# OpAMP_Sensor.net
KiCad netlist of a schematic drawn in Altium Designer
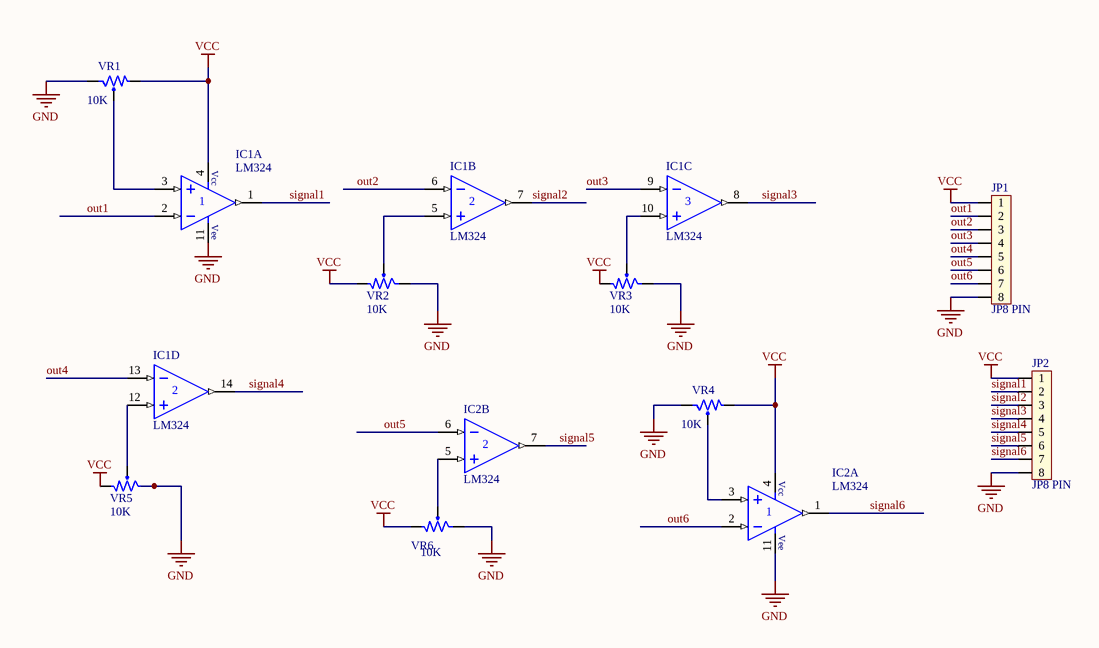
[diagram p0: OpAMP_Sensor.SchDoc]

(export (version "E")
  (design (tool "Eeschema 10.0.6"))
  (components
    (comp (ref "IC1")
      (value "LM324")
      (footprint "DIP14/W0.3")
      (description "Op x 4")
      (libsource (lib "syhaunguyen") (part "LM324"))
    )
    (comp (ref "IC2")
      (value "LM324")
      (footprint "DIP14/W0.3")
      (description "Op x 4")
      (libsource (lib "syhaunguyen") (part "LM324"))
    )
    (comp (ref "JP1") (value "JP8 PIN") (footprint "JP8") (libsource (lib "syhaunguyen") (part "JP8")))
    (comp (ref "JP2") (value "JP8 PIN") (footprint "JP8") (libsource (lib "syhaunguyen") (part "JP8")))
    (comp (ref "VR1")
      (value "10K")
      (footprint "VR")
      (description "Var Resistor")
      (libsource (lib "syhaunguyen") (part "VR1"))
    )
    (comp (ref "VR2")
      (value "10K")
      (footprint "VR")
      (description "Var Resistor")
      (libsource (lib "syhaunguyen") (part "VR1"))
    )
    (comp (ref "VR3")
      (value "10K")
      (footprint "VR")
      (description "Var Resistor")
      (libsource (lib "syhaunguyen") (part "VR1"))
    )
    (comp (ref "VR4")
      (value "10K")
      (footprint "VR")
      (description "Var Resistor")
      (libsource (lib "syhaunguyen") (part "VR1"))
    )
    (comp (ref "VR5")
      (value "10K")
      (footprint "VR")
      (description "Var Resistor")
      (libsource (lib "syhaunguyen") (part "VR1"))
    )
    (comp (ref "VR6")
      (value "10K")
      (footprint "VR")
      (description "Var Resistor")
      (libsource (lib "syhaunguyen") (part "VR1"))
    )
  )
  (nets
    (net (code "1") (name "/out1") (class "Default")
      (node (ref "IC1") (pin "2") (pinfunction "IN-_2") (pintype "input"))
      (node (ref "JP1") (pin "2") (pinfunction "2_2") (pintype "passive"))
    )
    (net (code "2") (name "/out2") (class "Default")
      (node (ref "IC1") (pin "6") (pinfunction "IN-_6") (pintype "input"))
      (node (ref "JP1") (pin "3") (pinfunction "3_3") (pintype "passive"))
    )
    (net (code "3") (name "/out3") (class "Default")
      (node (ref "IC1") (pin "9") (pinfunction "IN-_9") (pintype "input"))
      (node (ref "JP1") (pin "4") (pinfunction "4_4") (pintype "passive"))
    )
    (net (code "4") (name "/out4") (class "Default")
      (node (ref "IC1") (pin "13") (pinfunction "IN-_13") (pintype "input"))
      (node (ref "JP1") (pin "5") (pinfunction "5_5") (pintype "passive"))
    )
    (net (code "5") (name "/out5") (class "Default")
      (node (ref "IC2") (pin "6") (pinfunction "IN-_6") (pintype "input"))
      (node (ref "JP1") (pin "6") (pinfunction "6_6") (pintype "passive"))
    )
    (net (code "6") (name "/out6") (class "Default")
      (node (ref "IC2") (pin "2") (pinfunction "IN-_2") (pintype "input"))
      (node (ref "JP1") (pin "7") (pinfunction "7_7") (pintype "passive"))
    )
    (net (code "7") (name "/signal1") (class "Default")
      (node (ref "IC1") (pin "1") (pinfunction "OUT_1") (pintype "output"))
      (node (ref "JP2") (pin "2") (pinfunction "2_2") (pintype "passive"))
    )
    (net (code "8") (name "/signal2") (class "Default")
      (node (ref "IC1") (pin "7") (pinfunction "OUT_7") (pintype "output"))
      (node (ref "JP2") (pin "3") (pinfunction "3_3") (pintype "passive"))
    )
    (net (code "9") (name "/signal3") (class "Default")
      (node (ref "IC1") (pin "8") (pinfunction "OUT_8") (pintype "output"))
      (node (ref "JP2") (pin "4") (pinfunction "4_4") (pintype "passive"))
    )
    (net (code "10") (name "/signal4") (class "Default")
      (node (ref "IC1") (pin "14") (pinfunction "OUT_14") (pintype "output"))
      (node (ref "JP2") (pin "5") (pinfunction "5_5") (pintype "passive"))
    )
    (net (code "11") (name "/signal5") (class "Default")
      (node (ref "IC2") (pin "7") (pinfunction "OUT_7") (pintype "output"))
      (node (ref "JP2") (pin "6") (pinfunction "6_6") (pintype "passive"))
    )
    (net (code "12") (name "/signal6") (class "Default")
      (node (ref "IC2") (pin "1") (pinfunction "OUT_1") (pintype "output"))
      (node (ref "JP2") (pin "7") (pinfunction "7_7") (pintype "passive"))
    )
    (net (code "13") (name "GND") (class "Default")
      (node (ref "IC1") (pin "11") (pinfunction "V-_11") (pintype "power_in"))
      (node (ref "IC2") (pin "11") (pinfunction "V-_11") (pintype "power_in"))
      (node (ref "JP1") (pin "8") (pinfunction "8_8") (pintype "passive"))
      (node (ref "JP2") (pin "8") (pinfunction "8_8") (pintype "passive"))
      (node (ref "VR1") (pin "3") (pinfunction "3_3") (pintype "passive"))
      (node (ref "VR2") (pin "3") (pinfunction "3_3") (pintype "passive"))
      (node (ref "VR3") (pin "3") (pinfunction "3_3") (pintype "passive"))
      (node (ref "VR4") (pin "3") (pinfunction "3_3") (pintype "passive"))
      (node (ref "VR5") (pin "3") (pinfunction "3_3") (pintype "passive"))
      (node (ref "VR6") (pin "3") (pinfunction "3_3") (pintype "passive"))
    )
    (net (code "14") (name "Net-(IC1A-IN+)") (class "Default")
      (node (ref "IC1") (pin "3") (pinfunction "IN+_3") (pintype "input"))
      (node (ref "VR1") (pin "2") (pinfunction "2_2") (pintype "passive"))
    )
    (net (code "15") (name "Net-(IC1B-IN+)") (class "Default")
      (node (ref "IC1") (pin "5") (pinfunction "IN+_5") (pintype "input"))
      (node (ref "VR2") (pin "2") (pinfunction "2_2") (pintype "passive"))
    )
    (net (code "16") (name "Net-(IC1C-IN+)") (class "Default")
      (node (ref "IC1") (pin "10") (pinfunction "IN+_10") (pintype "input"))
      (node (ref "VR3") (pin "2") (pinfunction "2_2") (pintype "passive"))
    )
    (net (code "17") (name "Net-(IC1D-IN+)") (class "Default")
      (node (ref "IC1") (pin "12") (pinfunction "IN+_12") (pintype "input"))
      (node (ref "VR5") (pin "2") (pinfunction "2_2") (pintype "passive"))
    )
    (net (code "18") (name "Net-(IC2A-IN+)") (class "Default")
      (node (ref "IC2") (pin "3") (pinfunction "IN+_3") (pintype "input"))
      (node (ref "VR4") (pin "2") (pinfunction "2_2") (pintype "passive"))
    )
    (net (code "19") (name "Net-(IC2B-IN+)") (class "Default")
      (node (ref "IC2") (pin "5") (pinfunction "IN+_5") (pintype "input"))
      (node (ref "VR6") (pin "2") (pinfunction "2_2") (pintype "passive"))
    )
    (net (code "20") (name "VCC") (class "Default")
      (node (ref "IC1") (pin "4") (pinfunction "V+_4") (pintype "power_in"))
      (node (ref "IC2") (pin "4") (pinfunction "V+_4") (pintype "power_in"))
      (node (ref "JP1") (pin "1") (pinfunction "1_1") (pintype "passive"))
      (node (ref "JP2") (pin "1") (pinfunction "1_1") (pintype "passive"))
      (node (ref "VR1") (pin "1") (pinfunction "1_1") (pintype "passive"))
      (node (ref "VR2") (pin "1") (pinfunction "1_1") (pintype "passive"))
      (node (ref "VR3") (pin "1") (pinfunction "1_1") (pintype "passive"))
      (node (ref "VR4") (pin "1") (pinfunction "1_1") (pintype "passive"))
      (node (ref "VR5") (pin "1") (pinfunction "1_1") (pintype "passive"))
      (node (ref "VR6") (pin "1") (pinfunction "1_1") (pintype "passive"))
    )
  )
)
